# 3_3V_Regulator.net
KiCad netlist of a schematic drawn in Altium Designer
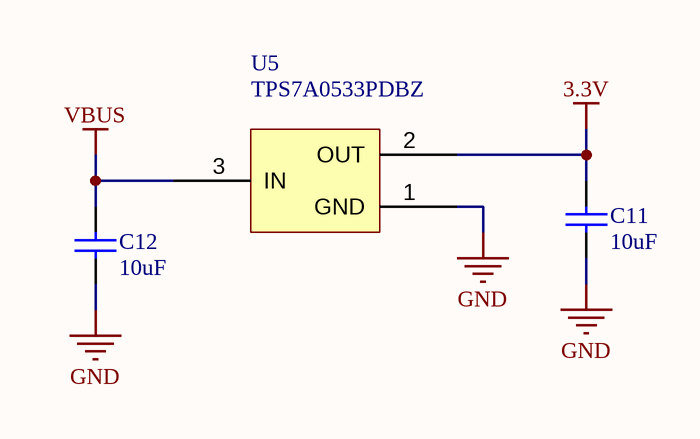
[diagram p0: 3.3V Regulator.SchDoc]

(export (version "E")
  (design (tool "Eeschema 10.0.6"))
  (components
    (comp (ref "C11") (value "10uF") (footprint "Capacitor 0603") (libsource (lib "x-io") (part "Capacitor")))
    (comp (ref "C12") (value "10uF") (footprint "Capacitor 0603") (libsource (lib "x-io") (part "Capacitor")))
    (comp (ref "U5")
      (value "TPS7A0533PDBZ")
      (footprint "SOT-23")
      (libsource (lib "x-io") (part "TPS7A0533PDBZ"))
    )
  )
  (nets
    (net (code "1") (name "3.3V") (class "Default")
      (node (ref "C11") (pin "2") (pinfunction "2_2") (pintype "passive"))
      (node (ref "U5") (pin "2") (pinfunction "OUT_2") (pintype "passive"))
    )
    (net (code "2") (name "GND") (class "Default")
      (node (ref "C11") (pin "1") (pinfunction "1_1") (pintype "passive"))
      (node (ref "C12") (pin "1") (pinfunction "1_1") (pintype "passive"))
      (node (ref "U5") (pin "1") (pinfunction "GND_1") (pintype "passive"))
    )
    (net (code "3") (name "VBUS") (class "Default")
      (node (ref "C12") (pin "2") (pinfunction "2_2") (pintype "passive"))
      (node (ref "U5") (pin "3") (pinfunction "IN_3") (pintype "passive"))
    )
  )
)
